# micro_controller.net
KiCad netlist of a schematic drawn in Altium Designer
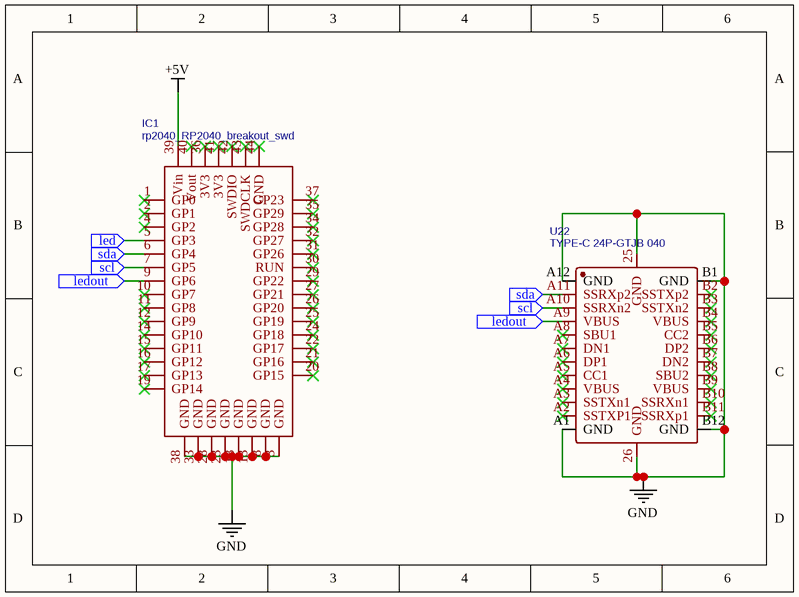
[diagram p0: micro_controller.schdoc]

(export (version "E")
  (design (tool "Eeschema 10.0.6"))
  (components
    (comp (ref "IC1")
      (value "rp2040_RP2040_breakout_swd")
      (fields (field (name "CONTRIBUTOR") "rataweb"))
      (libsource (lib "altium-import") (part "root_0_rp2040_RP2040_breakout_swd_"))
    )
    (comp (ref "U22")
      (value "TYPE-C 24P-GTJB 040")
      (fields (field (name "MANUFACTURER") "SHOU HAN(首韩)") (field (name "CONTRIBUTOR") "lcsc"))
      (libsource (lib "altium-import") (part "root_0_TYPE-C 24P-GTJB 040_"))
    )
  )
  (nets
    (net (code "1") (name "+5V") (class "Default")
      (node (ref "IC1") (pin "39") (pinfunction "Vin_39") (pintype "passive"))
    )
    (net (code "2") (name "/led") (class "Default")
      (node (ref "IC1") (pin "5") (pinfunction "GP3_5") (pintype "passive"))
    )
    (net (code "3") (name "/ledout") (class "Default")
      (node (ref "IC1") (pin "9") (pinfunction "GP6_9") (pintype "passive"))
      (node (ref "U22") (pin "A9") (pinfunction "VBUS_A9") (pintype "passive"))
    )
    (net (code "4") (name "/scl") (class "Default")
      (node (ref "IC1") (pin "7") (pinfunction "GP5_7") (pintype "passive"))
      (node (ref "U22") (pin "A10") (pinfunction "SSRXn2_A10") (pintype "passive"))
    )
    (net (code "5") (name "/sda") (class "Default")
      (node (ref "IC1") (pin "6") (pinfunction "GP4_6") (pintype "passive"))
      (node (ref "U22") (pin "A11") (pinfunction "SSRXp2_A11") (pintype "passive"))
    )
    (net (code "6") (name "GND") (class "Default")
      (node (ref "IC1") (pin "13") (pinfunction "GND_13") (pintype "passive"))
      (node (ref "IC1") (pin "18") (pinfunction "GND_18") (pintype "passive"))
      (node (ref "IC1") (pin "23") (pinfunction "GND_23") (pintype "passive"))
      (node (ref "IC1") (pin "28") (pinfunction "GND_28") (pintype "passive"))
      (node (ref "IC1") (pin "3") (pinfunction "GND_3") (pintype "passive"))
      (node (ref "IC1") (pin "33") (pinfunction "GND_33") (pintype "passive"))
      (node (ref "IC1") (pin "38") (pinfunction "GND_38") (pintype "passive"))
      (node (ref "IC1") (pin "8") (pinfunction "GND_8") (pintype "passive"))
      (node (ref "U22") (pin "25") (pinfunction "GND_25") (pintype "passive"))
      (node (ref "U22") (pin "26") (pinfunction "GND_26") (pintype "passive"))
      (node (ref "U22") (pin "A1") (pinfunction "GND_A1") (pintype "passive"))
      (node (ref "U22") (pin "A12") (pinfunction "GND_A12") (pintype "passive"))
      (node (ref "U22") (pin "B1") (pinfunction "GND_B1") (pintype "passive"))
      (node (ref "U22") (pin "B12") (pinfunction "GND_B12") (pintype "passive"))
    )
    (net (code "7") (name "unconnected-(IC1-3V3-Pad36)") (class "Default")
      (node (ref "IC1") (pin "36") (pinfunction "3V3_36") (pintype "passive+no_connect"))
    )
    (net (code "8") (name "unconnected-(IC1-3V3-Pad41)") (class "Default")
      (node (ref "IC1") (pin "41") (pinfunction "3V3_41") (pintype "passive+no_connect"))
    )
    (net (code "9") (name "unconnected-(IC1-GND-Pad44)") (class "Default")
      (node (ref "IC1") (pin "44") (pinfunction "GND_44") (pintype "passive+no_connect"))
    )
    (net (code "10") (name "unconnected-(IC1-GP0-Pad1)") (class "Default")
      (node (ref "IC1") (pin "1") (pinfunction "GP0_1") (pintype "passive+no_connect"))
    )
    (net (code "11") (name "unconnected-(IC1-GP1-Pad2)") (class "Default")
      (node (ref "IC1") (pin "2") (pinfunction "GP1_2") (pintype "passive+no_connect"))
    )
    (net (code "12") (name "unconnected-(IC1-GP2-Pad4)") (class "Default")
      (node (ref "IC1") (pin "4") (pinfunction "GP2_4") (pintype "passive+no_connect"))
    )
    (net (code "13") (name "unconnected-(IC1-GP7-Pad10)") (class "Default")
      (node (ref "IC1") (pin "10") (pinfunction "GP7_10") (pintype "passive+no_connect"))
    )
    (net (code "14") (name "unconnected-(IC1-GP8-Pad11)") (class "Default")
      (node (ref "IC1") (pin "11") (pinfunction "GP8_11") (pintype "passive+no_connect"))
    )
    (net (code "15") (name "unconnected-(IC1-GP9-Pad12)") (class "Default")
      (node (ref "IC1") (pin "12") (pinfunction "GP9_12") (pintype "passive+no_connect"))
    )
    (net (code "16") (name "unconnected-(IC1-GP10-Pad14)") (class "Default")
      (node (ref "IC1") (pin "14") (pinfunction "GP10_14") (pintype "passive+no_connect"))
    )
    (net (code "17") (name "unconnected-(IC1-GP11-Pad15)") (class "Default")
      (node (ref "IC1") (pin "15") (pinfunction "GP11_15") (pintype "passive+no_connect"))
    )
    (net (code "18") (name "unconnected-(IC1-GP12-Pad16)") (class "Default")
      (node (ref "IC1") (pin "16") (pinfunction "GP12_16") (pintype "passive+no_connect"))
    )
    (net (code "19") (name "unconnected-(IC1-GP13-Pad17)") (class "Default")
      (node (ref "IC1") (pin "17") (pinfunction "GP13_17") (pintype "passive+no_connect"))
    )
    (net (code "20") (name "unconnected-(IC1-GP14-Pad19)") (class "Default")
      (node (ref "IC1") (pin "19") (pinfunction "GP14_19") (pintype "passive+no_connect"))
    )
    (net (code "21") (name "unconnected-(IC1-GP15-Pad20)") (class "Default")
      (node (ref "IC1") (pin "20") (pinfunction "GP15_20") (pintype "passive+no_connect"))
    )
    (net (code "22") (name "unconnected-(IC1-GP16-Pad21)") (class "Default")
      (node (ref "IC1") (pin "21") (pinfunction "GP16_21") (pintype "passive+no_connect"))
    )
    (net (code "23") (name "unconnected-(IC1-GP17-Pad22)") (class "Default")
      (node (ref "IC1") (pin "22") (pinfunction "GP17_22") (pintype "passive+no_connect"))
    )
    (net (code "24") (name "unconnected-(IC1-GP18-Pad24)") (class "Default")
      (node (ref "IC1") (pin "24") (pinfunction "GP18_24") (pintype "passive+no_connect"))
    )
    (net (code "25") (name "unconnected-(IC1-GP19-Pad25)") (class "Default")
      (node (ref "IC1") (pin "25") (pinfunction "GP19_25") (pintype "passive+no_connect"))
    )
    (net (code "26") (name "unconnected-(IC1-GP20-Pad26)") (class "Default")
      (node (ref "IC1") (pin "26") (pinfunction "GP20_26") (pintype "passive+no_connect"))
    )
    (net (code "27") (name "unconnected-(IC1-GP21-Pad27)") (class "Default")
      (node (ref "IC1") (pin "27") (pinfunction "GP21_27") (pintype "passive+no_connect"))
    )
    (net (code "28") (name "unconnected-(IC1-GP22-Pad29)") (class "Default")
      (node (ref "IC1") (pin "29") (pinfunction "GP22_29") (pintype "passive+no_connect"))
    )
    (net (code "29") (name "unconnected-(IC1-GP23-Pad37)") (class "Default")
      (node (ref "IC1") (pin "37") (pinfunction "GP23_37") (pintype "passive+no_connect"))
    )
    (net (code "30") (name "unconnected-(IC1-GP26-Pad31)") (class "Default")
      (node (ref "IC1") (pin "31") (pinfunction "GP26_31") (pintype "passive+no_connect"))
    )
    (net (code "31") (name "unconnected-(IC1-GP27-Pad32)") (class "Default")
      (node (ref "IC1") (pin "32") (pinfunction "GP27_32") (pintype "passive+no_connect"))
    )
    (net (code "32") (name "unconnected-(IC1-GP28-Pad34)") (class "Default")
      (node (ref "IC1") (pin "34") (pinfunction "GP28_34") (pintype "passive+no_connect"))
    )
    (net (code "33") (name "unconnected-(IC1-GP29-Pad35)") (class "Default")
      (node (ref "IC1") (pin "35") (pinfunction "GP29_35") (pintype "passive+no_connect"))
    )
    (net (code "34") (name "unconnected-(IC1-RUN-Pad30)") (class "Default")
      (node (ref "IC1") (pin "30") (pinfunction "RUN_30") (pintype "passive+no_connect"))
    )
    (net (code "35") (name "unconnected-(IC1-SWDCLK-Pad43)") (class "Default")
      (node (ref "IC1") (pin "43") (pinfunction "SWDCLK_43") (pintype "passive+no_connect"))
    )
    (net (code "36") (name "unconnected-(IC1-SWDIO-Pad42)") (class "Default")
      (node (ref "IC1") (pin "42") (pinfunction "SWDIO_42") (pintype "passive+no_connect"))
    )
    (net (code "37") (name "unconnected-(IC1-Vout-Pad40)") (class "Default")
      (node (ref "IC1") (pin "40") (pinfunction "Vout_40") (pintype "passive+no_connect"))
    )
    (net (code "38") (name "unconnected-(U22-CC1-PadA5)") (class "Default")
      (node (ref "U22") (pin "A5") (pinfunction "CC1_A5") (pintype "passive+no_connect"))
    )
    (net (code "39") (name "unconnected-(U22-CC2-PadB5)") (class "Default")
      (node (ref "U22") (pin "B5") (pinfunction "CC2_B5") (pintype "passive+no_connect"))
    )
    (net (code "40") (name "unconnected-(U22-DN1-PadA7)") (class "Default")
      (node (ref "U22") (pin "A7") (pinfunction "DN1_A7") (pintype "passive+no_connect"))
    )
    (net (code "41") (name "unconnected-(U22-DN2-PadB7)") (class "Default")
      (node (ref "U22") (pin "B7") (pinfunction "DN2_B7") (pintype "passive+no_connect"))
    )
    (net (code "42") (name "unconnected-(U22-DP1-PadA6)") (class "Default")
      (node (ref "U22") (pin "A6") (pinfunction "DP1_A6") (pintype "passive+no_connect"))
    )
    (net (code "43") (name "unconnected-(U22-DP2-PadB6)") (class "Default")
      (node (ref "U22") (pin "B6") (pinfunction "DP2_B6") (pintype "passive+no_connect"))
    )
    (net (code "44") (name "unconnected-(U22-SBU1-PadA8)") (class "Default")
      (node (ref "U22") (pin "A8") (pinfunction "SBU1_A8") (pintype "passive+no_connect"))
    )
    (net (code "45") (name "unconnected-(U22-SBU2-PadB8)") (class "Default")
      (node (ref "U22") (pin "B8") (pinfunction "SBU2_B8") (pintype "passive+no_connect"))
    )
    (net (code "46") (name "unconnected-(U22-SSRXn1-PadB10)") (class "Default")
      (node (ref "U22") (pin "B10") (pinfunction "SSRXn1_B10") (pintype "passive+no_connect"))
    )
    (net (code "47") (name "unconnected-(U22-SSRXp1-PadB11)") (class "Default")
      (node (ref "U22") (pin "B11") (pinfunction "SSRXp1_B11") (pintype "passive+no_connect"))
    )
    (net (code "48") (name "unconnected-(U22-SSTXP1-PadA2)") (class "Default")
      (node (ref "U22") (pin "A2") (pinfunction "SSTXP1_A2") (pintype "passive+no_connect"))
    )
    (net (code "49") (name "unconnected-(U22-SSTXn1-PadA3)") (class "Default")
      (node (ref "U22") (pin "A3") (pinfunction "SSTXn1_A3") (pintype "passive+no_connect"))
    )
    (net (code "50") (name "unconnected-(U22-SSTXn2-PadB3)") (class "Default")
      (node (ref "U22") (pin "B3") (pinfunction "SSTXn2_B3") (pintype "passive+no_connect"))
    )
    (net (code "51") (name "unconnected-(U22-SSTXp2-PadB2)") (class "Default")
      (node (ref "U22") (pin "B2") (pinfunction "SSTXp2_B2") (pintype "passive+no_connect"))
    )
    (net (code "52") (name "unconnected-(U22-VBUS-PadA4)") (class "Default")
      (node (ref "U22") (pin "A4") (pinfunction "VBUS_A4") (pintype "passive+no_connect"))
    )
    (net (code "53") (name "unconnected-(U22-VBUS-PadB4)") (class "Default")
      (node (ref "U22") (pin "B4") (pinfunction "VBUS_B4") (pintype "passive+no_connect"))
    )
    (net (code "54") (name "unconnected-(U22-VBUS-PadB9)") (class "Default")
      (node (ref "U22") (pin "B9") (pinfunction "VBUS_B9") (pintype "passive+no_connect"))
    )
  )
)
